# nav_module.net
KiCad netlist of a schematic drawn in EAGLE
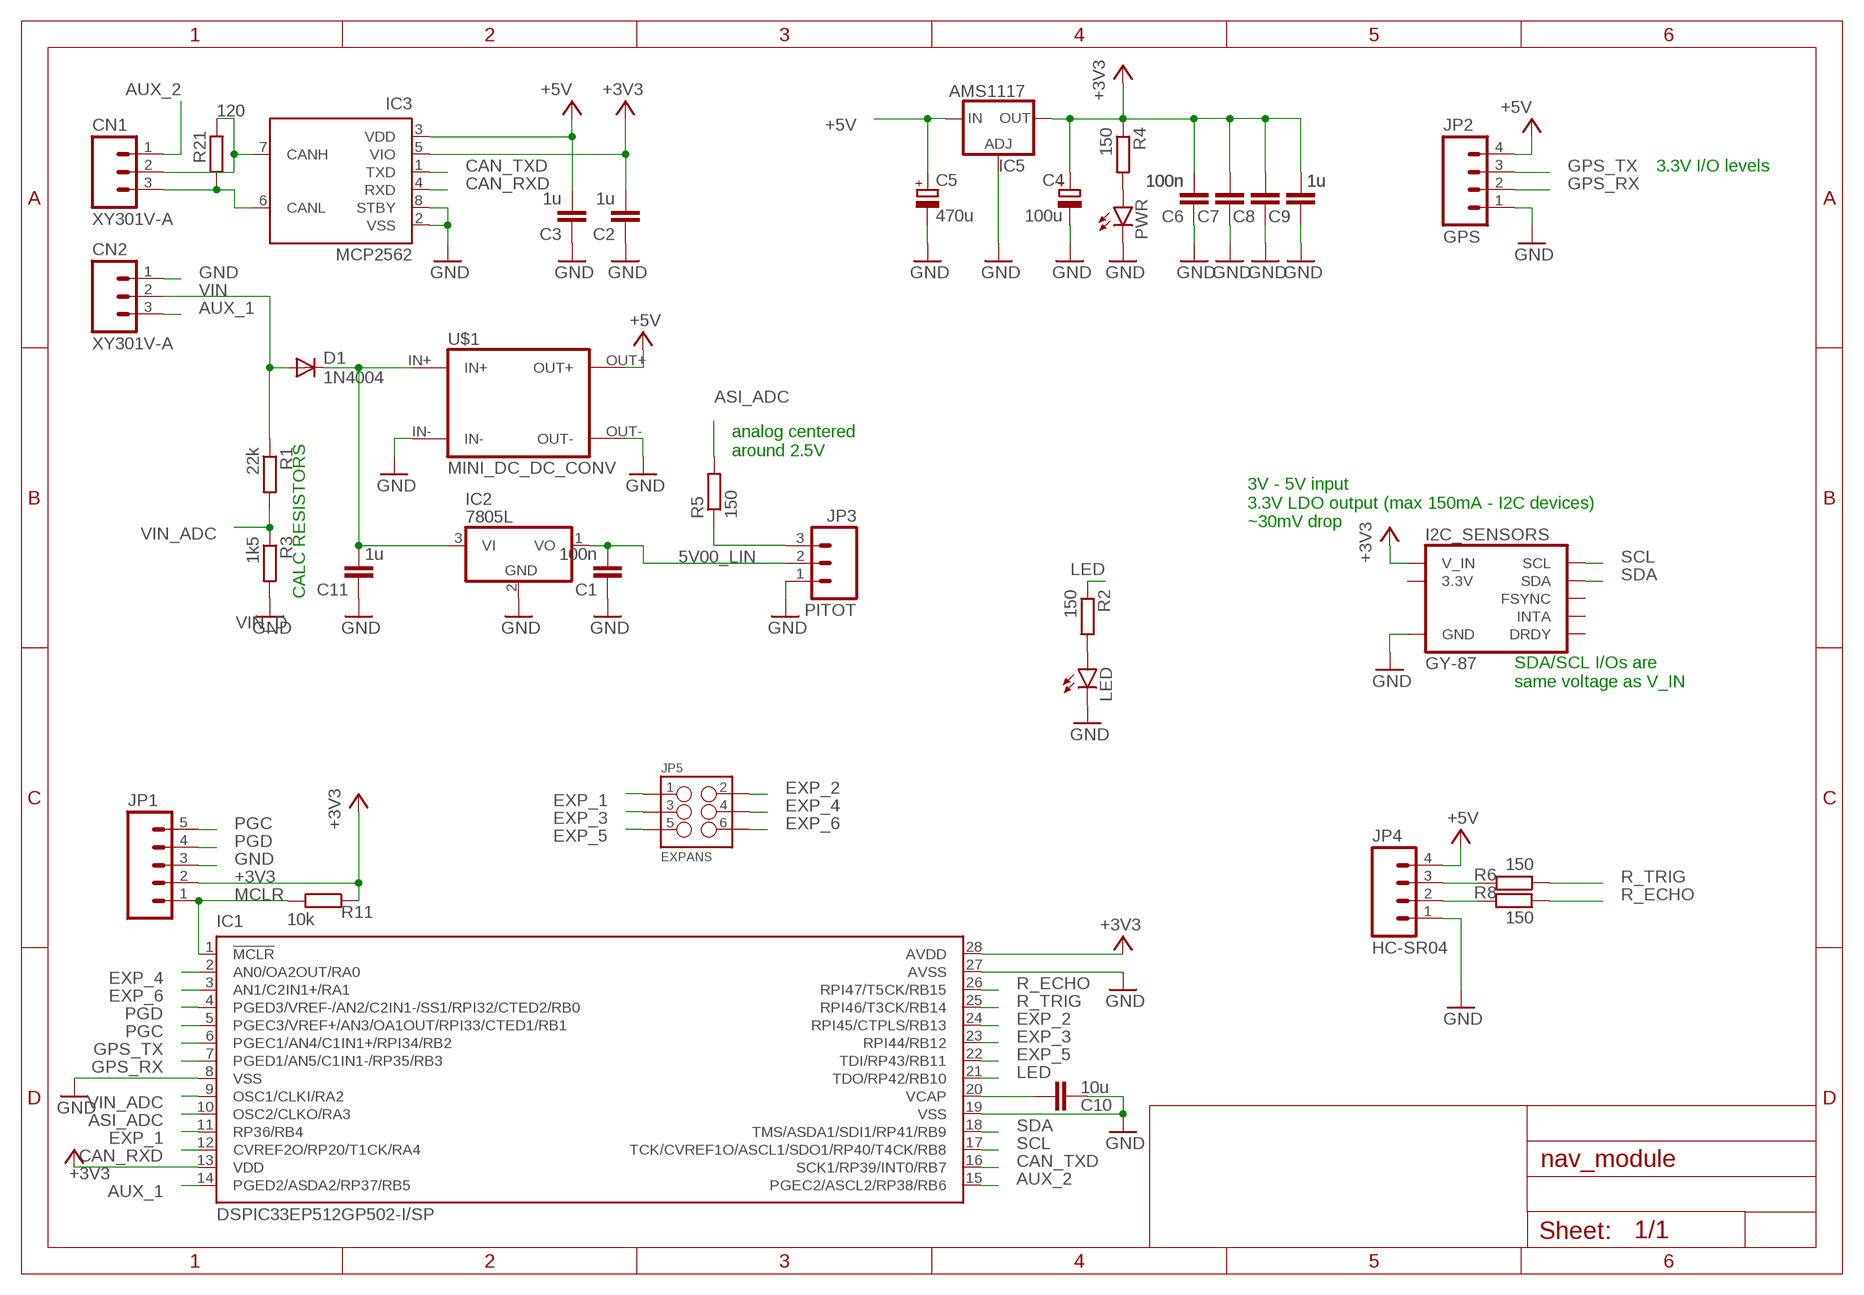
[diagram p0: schematic, sheet 1]

(export (version "E")
  (design (tool "Eeschema 10.0.6"))
  (components
    (comp (ref "C1")
      (value "100n")
      (footprint "eagle-import:C0603K")
      (libsource (lib "eagle-import") (part "C-EUC0603K"))
    )
    (comp (ref "C2")
      (value "1u")
      (footprint "eagle-import:C0603K")
      (libsource (lib "eagle-import") (part "C-EUC0603K"))
    )
    (comp (ref "C3")
      (value "1u")
      (footprint "eagle-import:C0603K")
      (libsource (lib "eagle-import") (part "C-EUC0603K"))
    )
    (comp (ref "C4")
      (value "100u")
      (footprint "eagle-import:E2,5-7")
      (libsource (lib "eagle-import") (part "CPOL-EUE2.5-7"))
    )
    (comp (ref "C5")
      (value "470u")
      (footprint "eagle-import:E3,5-8")
      (libsource (lib "eagle-import") (part "CPOL-EUE3.5-8"))
    )
    (comp (ref "C6")
      (value "100n")
      (footprint "eagle-import:C0603K")
      (libsource (lib "eagle-import") (part "C-EUC0603K"))
    )
    (comp (ref "C7")
      (value "100n")
      (footprint "eagle-import:C0603K")
      (libsource (lib "eagle-import") (part "C-EUC0603K"))
    )
    (comp (ref "C8")
      (value "1u")
      (footprint "eagle-import:C0603K")
      (libsource (lib "eagle-import") (part "C-EUC0603K"))
    )
    (comp (ref "C9")
      (value "1u")
      (footprint "eagle-import:C0603K")
      (libsource (lib "eagle-import") (part "C-EUC0603K"))
    )
    (comp (ref "C10")
      (value "10u")
      (footprint "eagle-import:C025-030X050")
      (libsource (lib "eagle-import") (part "C-EU025-030X050"))
    )
    (comp (ref "C11")
      (value "1u")
      (footprint "eagle-import:C0603K")
      (libsource (lib "eagle-import") (part "C-EUC0603K"))
    )
    (comp (ref "CN1")
      (value "XY301V-A")
      (footprint "eagle-import:XY301V-A")
      (libsource (lib "eagle-import") (part "XY301V-A"))
    )
    (comp (ref "CN2")
      (value "XY301V-A")
      (footprint "eagle-import:XY301V-A")
      (libsource (lib "eagle-import") (part "XY301V-A"))
    )
    (comp (ref "D1")
      (value "1N4004")
      (footprint "eagle-import:DO41-10")
      (libsource (lib "eagle-import") (part "1N4004"))
    )
    (comp (ref "I2C_SENSORS")
      (value "GY-87")
      (footprint "eagle-import:GY-87")
      (libsource (lib "eagle-import") (part "GY-87"))
    )
    (comp (ref "IC1")
      (value "DSPIC33EP512GP502-I/SP")
      (footprint "eagle-import:DIL28-3")
      (libsource (lib "eagle-import") (part "DSPIC33EP512502-I/SPGP"))
    )
    (comp (ref "IC2")
      (value "7805L")
      (footprint "eagle-import:TO92")
      (libsource (lib "eagle-import") (part "78L05"))
    )
    (comp (ref "IC3")
      (value "MCP2562")
      (footprint "eagle-import:DIL8")
      (libsource (lib "eagle-import") (part "MCP2562-E/P"))
    )
    (comp (ref "IC5")
      (value "AMS1117")
      (footprint "eagle-import:SOT223")
      (libsource (lib "eagle-import") (part "LD117A?S33TR"))
    )
    (comp (ref "JP1")
      (value "M05PTH")
      (footprint "eagle-import:1X05")
      (libsource (lib "eagle-import") (part "M05PTH"))
    )
    (comp (ref "JP2")
      (value "GPS")
      (footprint "eagle-import:1X04")
      (libsource (lib "eagle-import") (part "M04PTH"))
    )
    (comp (ref "JP3")
      (value "PITOT")
      (footprint "eagle-import:1X03")
      (libsource (lib "eagle-import") (part "M03PTH"))
    )
    (comp (ref "JP4")
      (value "HC-SR04")
      (footprint "eagle-import:1X04")
      (libsource (lib "eagle-import") (part "M04PTH"))
    )
    (comp (ref "JP5")
      (value "EXPANS")
      (footprint "eagle-import:2X3")
      (libsource (lib "eagle-import") (part "M03X2FEMALE"))
    )
    (comp (ref "LED")
      (value "LED-FKIT-1206")
      (footprint "eagle-import:FKIT-LED-1206")
      (libsource (lib "eagle-import") (part "LED-FKIT-1206"))
    )
    (comp (ref "PWR")
      (value "LED-FKIT-1206")
      (footprint "eagle-import:FKIT-LED-1206")
      (libsource (lib "eagle-import") (part "LED-FKIT-1206"))
    )
    (comp (ref "R1")
      (value "22k")
      (footprint "eagle-import:R0603")
      (libsource (lib "eagle-import") (part "R-EU_R0603"))
    )
    (comp (ref "R2")
      (value "150")
      (footprint "eagle-import:R0603")
      (libsource (lib "eagle-import") (part "R-EU_R0603"))
    )
    (comp (ref "R3")
      (value "1k5")
      (footprint "eagle-import:R0603")
      (libsource (lib "eagle-import") (part "R-EU_R0603"))
    )
    (comp (ref "R4")
      (value "150")
      (footprint "eagle-import:R0603")
      (libsource (lib "eagle-import") (part "R-EU_R0603"))
    )
    (comp (ref "R5")
      (value "150")
      (footprint "eagle-import:R0603")
      (libsource (lib "eagle-import") (part "R-EU_R0603"))
    )
    (comp (ref "R6")
      (value "150")
      (footprint "eagle-import:R0603")
      (libsource (lib "eagle-import") (part "R-EU_R0603"))
    )
    (comp (ref "R8")
      (value "150")
      (footprint "eagle-import:R0603")
      (libsource (lib "eagle-import") (part "R-EU_R0603"))
    )
    (comp (ref "R11")
      (value "10k")
      (footprint "eagle-import:R0603")
      (libsource (lib "eagle-import") (part "R-EU_R0603"))
    )
    (comp (ref "R21")
      (value "120")
      (footprint "eagle-import:R0603")
      (libsource (lib "eagle-import") (part "R-EU_R0603"))
    )
    (comp (ref "U$1")
      (value "MINI_DC_DC_CONV")
      (footprint "eagle-import:DSN-MINI-360")
      (libsource (lib "eagle-import") (part "MINI_DC_DC_CONV"))
    )
  )
  (nets
    (net (code "1") (name "+3V3") (class "Default")
      (node (ref "C2") (pin "2") (pinfunction "2_2") (pintype "passive"))
      (node (ref "C4") (pin "+") (pinfunction "+_+") (pintype "passive"))
      (node (ref "C6") (pin "2") (pinfunction "2_2") (pintype "passive"))
      (node (ref "C7") (pin "2") (pinfunction "2_2") (pintype "passive"))
      (node (ref "C8") (pin "2") (pinfunction "2_2") (pintype "passive"))
      (node (ref "C9") (pin "2") (pinfunction "2_2") (pintype "passive"))
      (node (ref "I2C_SENSORS") (pin "VCC_IN") (pinfunction "V_IN_VCC_IN") (pintype "power_in"))
      (node (ref "IC1") (pin "13") (pinfunction "VDD_13") (pintype "power_in"))
      (node (ref "IC1") (pin "28") (pinfunction "AVDD_28") (pintype "power_in"))
      (node (ref "IC3") (pin "5") (pinfunction "VIO_5") (pintype "power_in"))
      (node (ref "IC5") (pin "2") (pinfunction "OUT_2") (pintype "passive"))
      (node (ref "IC5") (pin "@2") (pinfunction "OUT_@2") (pintype "passive"))
      (node (ref "JP1") (pin "2") (pinfunction "2_2") (pintype "passive"))
      (node (ref "R11") (pin "1") (pinfunction "1_1") (pintype "passive"))
      (node (ref "R4") (pin "1") (pinfunction "1_1") (pintype "passive"))
    )
    (net (code "2") (name "+5V") (class "Default")
      (node (ref "C3") (pin "2") (pinfunction "2_2") (pintype "passive"))
      (node (ref "C5") (pin "+") (pinfunction "+_+") (pintype "passive"))
      (node (ref "IC3") (pin "3") (pinfunction "VDD_3") (pintype "power_in"))
      (node (ref "IC5") (pin "3") (pinfunction "IN_3") (pintype "input"))
      (node (ref "JP2") (pin "4") (pinfunction "4_4") (pintype "passive"))
      (node (ref "JP4") (pin "4") (pinfunction "4_4") (pintype "passive"))
      (node (ref "U$1") (pin "OUT+") (pinfunction "OUT+_OUT+") (pintype "output"))
    )
    (net (code "3") (name "/3.3V") (class "Default")
      (node (ref "I2C_SENSORS") (pin "3.3V") (pinfunction "3.3V_3.3V") (pintype "power_in"))
    )
    (net (code "4") (name "/5V00_LIN") (class "Default")
      (node (ref "C1") (pin "2") (pinfunction "2_2") (pintype "passive"))
      (node (ref "IC2") (pin "1") (pinfunction "VO_1") (pintype "passive"))
      (node (ref "JP3") (pin "2") (pinfunction "2_2") (pintype "passive"))
    )
    (net (code "5") (name "/ASI_ADC") (class "Default")
      (node (ref "IC1") (pin "10") (pinfunction "OSC2/CLKO/RA3_10") (pintype "bidirectional"))
      (node (ref "R5") (pin "2") (pinfunction "2_2") (pintype "passive"))
    )
    (net (code "6") (name "/AUX_1") (class "Default")
      (node (ref "CN2") (pin "3") (pinfunction "3_3") (pintype "passive"))
      (node (ref "IC1") (pin "14") (pinfunction "PGED2/ASDA2/RP37/RB5_14") (pintype "bidirectional"))
    )
    (net (code "7") (name "/AUX_2") (class "Default")
      (node (ref "CN1") (pin "1") (pinfunction "1_1") (pintype "passive"))
      (node (ref "IC1") (pin "15") (pinfunction "PGEC2/ASCL2/RP38/RB6_15") (pintype "bidirectional"))
    )
    (net (code "8") (name "/CAN_RXD") (class "Default")
      (node (ref "IC1") (pin "12") (pinfunction "CVREF2O/RP20/T1CK/RA4_12") (pintype "bidirectional"))
      (node (ref "IC3") (pin "4") (pinfunction "RXD_4") (pintype "output"))
    )
    (net (code "9") (name "/CAN_TXD") (class "Default")
      (node (ref "IC1") (pin "16") (pinfunction "SCK1/RP39/INT0/RB7_16") (pintype "bidirectional"))
      (node (ref "IC3") (pin "1") (pinfunction "TXD_1") (pintype "input"))
    )
    (net (code "10") (name "/EXP_1") (class "Default")
      (node (ref "IC1") (pin "11") (pinfunction "RP36/RB4_11") (pintype "bidirectional"))
      (node (ref "JP5") (pin "1") (pinfunction "1_1") (pintype "bidirectional"))
    )
    (net (code "11") (name "/EXP_2") (class "Default")
      (node (ref "IC1") (pin "24") (pinfunction "RPI45/CTPLS/RB13_24") (pintype "bidirectional"))
      (node (ref "JP5") (pin "2") (pinfunction "2_2") (pintype "bidirectional"))
    )
    (net (code "12") (name "/EXP_3") (class "Default")
      (node (ref "IC1") (pin "23") (pinfunction "RPI44/RB12_23") (pintype "bidirectional"))
      (node (ref "JP5") (pin "3") (pinfunction "3_3") (pintype "bidirectional"))
    )
    (net (code "13") (name "/EXP_4") (class "Default")
      (node (ref "IC1") (pin "2") (pinfunction "AN0/OA2OUT/RA0_2") (pintype "bidirectional"))
      (node (ref "JP5") (pin "4") (pinfunction "4_4") (pintype "bidirectional"))
    )
    (net (code "14") (name "/EXP_5") (class "Default")
      (node (ref "IC1") (pin "22") (pinfunction "TDI/RP43/RB11_22") (pintype "bidirectional"))
      (node (ref "JP5") (pin "5") (pinfunction "5_5") (pintype "bidirectional"))
    )
    (net (code "15") (name "/EXP_6") (class "Default")
      (node (ref "IC1") (pin "3") (pinfunction "AN1/C2IN1+/RA1_3") (pintype "bidirectional"))
      (node (ref "JP5") (pin "6") (pinfunction "6_6") (pintype "bidirectional"))
    )
    (net (code "16") (name "/GPS_RX") (class "Default")
      (node (ref "IC1") (pin "7") (pinfunction "PGED1/AN5/C1IN1-/RP35/RB3_7") (pintype "bidirectional"))
      (node (ref "JP2") (pin "2") (pinfunction "2_2") (pintype "passive"))
    )
    (net (code "17") (name "/GPS_TX") (class "Default")
      (node (ref "IC1") (pin "6") (pinfunction "PGEC1/AN4/C1IN1+/RPI34/RB2_6") (pintype "bidirectional"))
      (node (ref "JP2") (pin "3") (pinfunction "3_3") (pintype "passive"))
    )
    (net (code "18") (name "/LED") (class "Default")
      (node (ref "IC1") (pin "21") (pinfunction "TDO/RP42/RB10_21") (pintype "bidirectional"))
      (node (ref "R2") (pin "1") (pinfunction "1_1") (pintype "passive"))
    )
    (net (code "19") (name "/MCLR") (class "Default")
      (node (ref "IC1") (pin "1") (pinfunction "~{MCLR}_1") (pintype "input"))
      (node (ref "JP1") (pin "1") (pinfunction "1_1") (pintype "passive"))
      (node (ref "R11") (pin "2") (pinfunction "2_2") (pintype "passive"))
    )
    (net (code "20") (name "/PGC") (class "Default")
      (node (ref "IC1") (pin "5") (pinfunction "PGEC3/VREF+/AN3/OA1OUT/RPI33/CTED1/RB1_5") (pintype "bidirectional"))
      (node (ref "JP1") (pin "5") (pinfunction "5_5") (pintype "passive"))
    )
    (net (code "21") (name "/PGD") (class "Default")
      (node (ref "IC1") (pin "4") (pinfunction "PGED3/VREF-/AN2/C2IN1-/SS1/RPI32/CTED2/RB0_4") (pintype "bidirectional"))
      (node (ref "JP1") (pin "4") (pinfunction "4_4") (pintype "passive"))
    )
    (net (code "22") (name "/R_ECHO") (class "Default")
      (node (ref "IC1") (pin "26") (pinfunction "RPI47/T5CK/RB15_26") (pintype "bidirectional"))
      (node (ref "R8") (pin "2") (pinfunction "2_2") (pintype "passive"))
    )
    (net (code "23") (name "/R_TRIG") (class "Default")
      (node (ref "IC1") (pin "25") (pinfunction "RPI46/T3CK/RB14_25") (pintype "bidirectional"))
      (node (ref "R6") (pin "1") (pinfunction "1_1") (pintype "passive"))
    )
    (net (code "24") (name "/SCL") (class "Default")
      (node (ref "I2C_SENSORS") (pin "SCL") (pinfunction "SCL_SCL") (pintype "bidirectional"))
      (node (ref "IC1") (pin "17") (pinfunction "TCK/CVREF1O/ASCL1/SDO1/RP40/T4CK/RB8_17") (pintype "bidirectional"))
    )
    (net (code "25") (name "/SDA") (class "Default")
      (node (ref "I2C_SENSORS") (pin "SDA") (pinfunction "SDA_SDA") (pintype "bidirectional"))
      (node (ref "IC1") (pin "18") (pinfunction "TMS/ASDA1/SDI1/RP41/RB9_18") (pintype "bidirectional"))
    )
    (net (code "26") (name "/VIN") (class "Default")
      (node (ref "CN2") (pin "2") (pinfunction "2_2") (pintype "passive"))
      (node (ref "D1") (pin "A") (pinfunction "A_A") (pintype "passive"))
      (node (ref "R1") (pin "1") (pinfunction "1_1") (pintype "passive"))
    )
    (net (code "27") (name "/VIN_ADC") (class "Default")
      (node (ref "IC1") (pin "9") (pinfunction "OSC1/CLKI/RA2_9") (pintype "input"))
      (node (ref "R1") (pin "2") (pinfunction "2_2") (pintype "passive"))
      (node (ref "R3") (pin "1") (pinfunction "1_1") (pintype "passive"))
    )
    (net (code "28") (name "/VIN_D") (class "Default")
      (node (ref "C11") (pin "2") (pinfunction "2_2") (pintype "passive"))
      (node (ref "D1") (pin "C") (pinfunction "C_C") (pintype "passive"))
      (node (ref "IC2") (pin "3") (pinfunction "VI_3") (pintype "input"))
      (node (ref "U$1") (pin "IN+") (pinfunction "IN+_IN+") (pintype "input"))
    )
    (net (code "29") (name "GND") (class "Default")
      (node (ref "C1") (pin "1") (pinfunction "1_1") (pintype "passive"))
      (node (ref "C10") (pin "1") (pinfunction "1_1") (pintype "passive"))
      (node (ref "C11") (pin "1") (pinfunction "1_1") (pintype "passive"))
      (node (ref "C2") (pin "1") (pinfunction "1_1") (pintype "passive"))
      (node (ref "C3") (pin "1") (pinfunction "1_1") (pintype "passive"))
      (node (ref "C4") (pin "-") (pinfunction "-_-") (pintype "passive"))
      (node (ref "C5") (pin "-") (pinfunction "-_-") (pintype "passive"))
      (node (ref "C6") (pin "1") (pinfunction "1_1") (pintype "passive"))
      (node (ref "C7") (pin "1") (pinfunction "1_1") (pintype "passive"))
      (node (ref "C8") (pin "1") (pinfunction "1_1") (pintype "passive"))
      (node (ref "C9") (pin "1") (pinfunction "1_1") (pintype "passive"))
      (node (ref "CN2") (pin "1") (pinfunction "1_1") (pintype "passive"))
      (node (ref "I2C_SENSORS") (pin "GND") (pinfunction "GND_GND") (pintype "power_in"))
      (node (ref "IC1") (pin "19") (pinfunction "VSS_19") (pintype "power_in"))
      (node (ref "IC1") (pin "27") (pinfunction "AVSS_27") (pintype "power_in"))
      (node (ref "IC1") (pin "8") (pinfunction "VSS_8") (pintype "power_in"))
      (node (ref "IC2") (pin "2") (pinfunction "GND_2") (pintype "passive"))
      (node (ref "IC3") (pin "2") (pinfunction "VSS_2") (pintype "power_in"))
      (node (ref "IC3") (pin "8") (pinfunction "STBY_8") (pintype "input"))
      (node (ref "IC5") (pin "1") (pinfunction "ADJ_1") (pintype "input"))
      (node (ref "JP1") (pin "3") (pinfunction "3_3") (pintype "passive"))
      (node (ref "JP2") (pin "1") (pinfunction "1_1") (pintype "passive"))
      (node (ref "JP3") (pin "1") (pinfunction "1_1") (pintype "passive"))
      (node (ref "JP4") (pin "1") (pinfunction "1_1") (pintype "passive"))
      (node (ref "LED") (pin "C") (pinfunction "C_C") (pintype "passive"))
      (node (ref "PWR") (pin "C") (pinfunction "C_C") (pintype "passive"))
      (node (ref "R3") (pin "2") (pinfunction "2_2") (pintype "passive"))
      (node (ref "U$1") (pin "IN-") (pinfunction "IN-_IN-") (pintype "power_in"))
      (node (ref "U$1") (pin "OUT-") (pinfunction "OUT-_OUT-") (pintype "power_in"))
    )
    (net (code "30") (name "Net-(IC1-VCAP)") (class "Default")
      (node (ref "C10") (pin "2") (pinfunction "2_2") (pintype "passive"))
      (node (ref "IC1") (pin "20") (pinfunction "VCAP_20") (pintype "power_in"))
    )
    (net (code "31") (name "Net-(IC3-CANH)") (class "Default")
      (node (ref "CN1") (pin "2") (pinfunction "2_2") (pintype "passive"))
      (node (ref "IC3") (pin "7") (pinfunction "CANH_7") (pintype "bidirectional"))
      (node (ref "R21") (pin "2") (pinfunction "2_2") (pintype "passive"))
    )
    (net (code "32") (name "Net-(IC3-CANL)") (class "Default")
      (node (ref "CN1") (pin "3") (pinfunction "3_3") (pintype "passive"))
      (node (ref "IC3") (pin "6") (pinfunction "CANL_6") (pintype "bidirectional"))
      (node (ref "R21") (pin "1") (pinfunction "1_1") (pintype "passive"))
    )
    (net (code "33") (name "Net-(JP3-Pad3)") (class "Default")
      (node (ref "JP3") (pin "3") (pinfunction "3_3") (pintype "passive"))
      (node (ref "R5") (pin "1") (pinfunction "1_1") (pintype "passive"))
    )
    (net (code "34") (name "Net-(JP4-Pad2)") (class "Default")
      (node (ref "JP4") (pin "2") (pinfunction "2_2") (pintype "passive"))
      (node (ref "R8") (pin "1") (pinfunction "1_1") (pintype "passive"))
    )
    (net (code "35") (name "Net-(JP4-Pad3)") (class "Default")
      (node (ref "JP4") (pin "3") (pinfunction "3_3") (pintype "passive"))
      (node (ref "R6") (pin "2") (pinfunction "2_2") (pintype "passive"))
    )
    (net (code "36") (name "Net-(LED-PadA)") (class "Default")
      (node (ref "LED") (pin "A") (pinfunction "A_A") (pintype "passive"))
      (node (ref "R2") (pin "2") (pinfunction "2_2") (pintype "passive"))
    )
    (net (code "37") (name "Net-(PWR-PadA)") (class "Default")
      (node (ref "PWR") (pin "A") (pinfunction "A_A") (pintype "passive"))
      (node (ref "R4") (pin "2") (pinfunction "2_2") (pintype "passive"))
    )
    (net (code "38") (name "unconnected-(I2C_SENSORS-PadDRDY)") (class "Default")
      (node (ref "I2C_SENSORS") (pin "DRDY") (pinfunction "DRDY_DRDY") (pintype "output"))
    )
    (net (code "39") (name "unconnected-(I2C_SENSORS-PadFSYNC)") (class "Default")
      (node (ref "I2C_SENSORS") (pin "FSYNC") (pinfunction "FSYNC_FSYNC") (pintype "output"))
    )
    (net (code "40") (name "unconnected-(I2C_SENSORS-PadINTA)") (class "Default")
      (node (ref "I2C_SENSORS") (pin "INTA") (pinfunction "INTA_INTA") (pintype "output"))
    )
  )
)
